# 3v_i2c_Bean_OLED_Rev1_1.net
KiCad netlist of a schematic drawn in Altium Designer
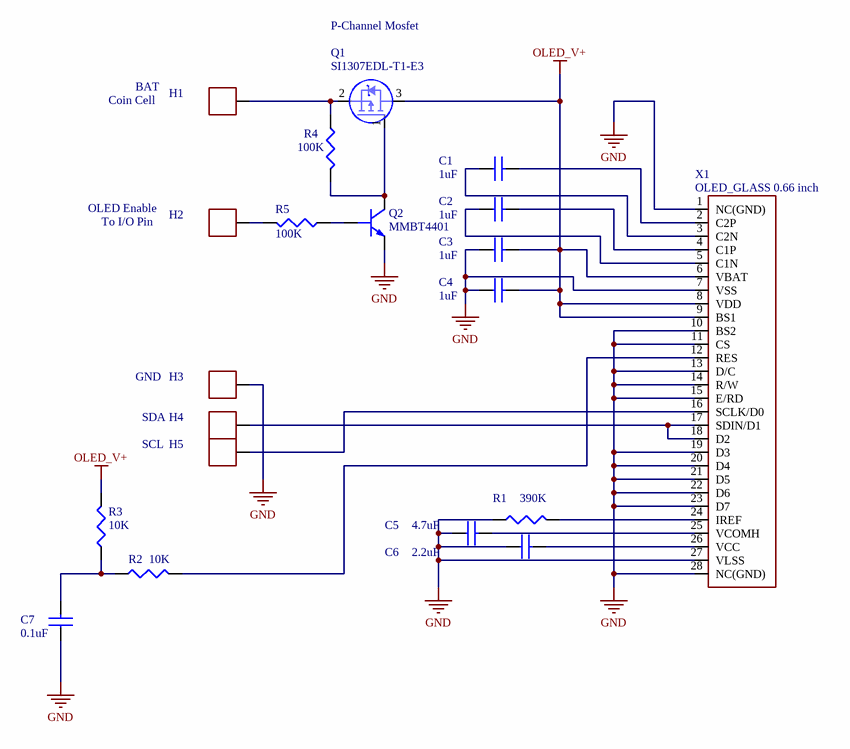
[diagram p0: 3v_i2c_Bean_OLED_Rev1.1.SchDoc]

(export (version "E")
  (design (tool "Eeschema 10.0.6"))
  (components
    (comp (ref "C1")
      (value "1uF")
      (footprint "CAPC1608X09L")
      (description "CAP 0603")
      (libsource (lib "Parts_Library") (part "CAP_0603"))
    )
    (comp (ref "C2")
      (value "1uF")
      (footprint "CAPC1608X09L")
      (description "CAP 0603")
      (libsource (lib "Parts_Library") (part "CAP_0603"))
    )
    (comp (ref "C3")
      (value "1uF")
      (footprint "CAPC1608X09L")
      (description "CAP 0603")
      (libsource (lib "Parts_Library") (part "CAP_0603"))
    )
    (comp (ref "C4")
      (value "1uF")
      (footprint "CAPC1608X09L")
      (description "CAP 0603")
      (libsource (lib "Parts_Library") (part "CAP_0603"))
    )
    (comp (ref "C5")
      (value "4.7uF")
      (footprint "CAPC1608X09L")
      (description "CAP 0603")
      (libsource (lib "Parts_Library") (part "CAP_0603"))
    )
    (comp (ref "C6")
      (value "2.2uF")
      (footprint "CAPC1608X09L")
      (description "CAP 0603")
      (libsource (lib "Parts_Library") (part "CAP_0603"))
    )
    (comp (ref "C7")
      (value "0.1uF")
      (footprint "CAPC1608X09L")
      (description "CAP 0603")
      (libsource (lib "Parts_Library") (part "CAP_0603"))
    )
    (comp (ref "H1")
      (value "CON1")
      (footprint "HDR1X1")
      (description "CONN HEADER 1POS .100\" PADS")
      (fields (field (name "PARTNUMBER") "PADS"))
      (libsource (lib "MAR") (part "CON1"))
    )
    (comp (ref "H2")
      (value "CON1")
      (footprint "HDR1X1")
      (description "CONN HEADER 1POS .100\" PADS")
      (fields (field (name "PARTNUMBER") "PADS"))
      (libsource (lib "MAR") (part "CON1"))
    )
    (comp (ref "H3")
      (value "CON1")
      (footprint "HDR1X1")
      (description "CONN HEADER 1POS .100\" PADS")
      (fields (field (name "PARTNUMBER") "PADS"))
      (libsource (lib "MAR") (part "CON1"))
    )
    (comp (ref "H4")
      (value "CON1")
      (footprint "HDR1X1")
      (description "CONN HEADER 1POS .100\" PADS")
      (fields (field (name "PARTNUMBER") "PADS"))
      (libsource (lib "MAR") (part "CON1"))
    )
    (comp (ref "H5")
      (value "CON1")
      (footprint "HDR1X1")
      (description "CONN HEADER 1POS .100\" PADS")
      (fields (field (name "PARTNUMBER") "PADS"))
      (libsource (lib "MAR") (part "CON1"))
    )
    (comp (ref "Q1")
      (value "~")
      (footprint "SC70-LB3_N")
      (description "MOSFET P-CH 12V 850MA SOT323-3")
      (fields (field (name "MANUFACTURER") "Vishay") (field (name "PARTNUMBER") "SI1307EDL-T1-E3"))
      (libsource (lib "MAR") (part "SI1307EDL-T1-E3"))
    )
    (comp (ref "Q2")
      (value "MMBT4401")
      (footprint "SOT95P240X110-3N")
      (description "TRANSISTOR GP NPN AMP SOT-23")
      (fields (field (name "MANUFACTURER") "Fairchild Semi") (field (name "PARTNUMBER") "MMBT4401"))
      (libsource (lib "MAR") (part "MMBT4401"))
    )
    (comp (ref "R1")
      (value "390K")
      (footprint "RESC1608X06L")
      (description "RES 0603")
      (libsource (lib "Parts_Library") (part "RES_0603"))
    )
    (comp (ref "R2")
      (value "10K")
      (footprint "RESC1608X06L")
      (description "RES 0603")
      (libsource (lib "Parts_Library") (part "RES_0603"))
    )
    (comp (ref "R3")
      (value "10K")
      (footprint "RESC1608X06L")
      (description "RES 0603")
      (libsource (lib "Parts_Library") (part "RES_0603"))
    )
    (comp (ref "R4")
      (value "100K")
      (footprint "RESC1608X06L")
      (description "RES 100K OHM 1/10W 1% 0603 SMD")
      (libsource (lib "Parts_Library") (part "RES_0603"))
    )
    (comp (ref "R5")
      (value "100K")
      (footprint "RESC1608X06L")
      (description "RES 100K OHM 1/10W 1% 0603 SMD")
      (libsource (lib "Parts_Library") (part "RES_0603"))
    )
    (comp (ref "X1")
      (value "OLED_GLASS 0.66 inch")
      (footprint "OLED_GLASS 0.66 INCH")
      (description "0.66 inch OLED_GLASS")
      (libsource (lib "MAR") (part "OLED_GLASS 0.66 inch"))
    )
  )
  (nets
    (net (code "1") (name "GND") (class "Default")
      (node (ref "C3") (pin "1") (pinfunction "1_1") (pintype "passive"))
      (node (ref "C4") (pin "1") (pinfunction "1_1") (pintype "passive"))
      (node (ref "C5") (pin "1") (pinfunction "1_1") (pintype "passive"))
      (node (ref "C6") (pin "1") (pinfunction "1_1") (pintype "passive"))
      (node (ref "C7") (pin "1") (pinfunction "1_1") (pintype "passive"))
      (node (ref "H3") (pin "1") (pintype "passive"))
      (node (ref "Q2") (pin "2") (pinfunction "E_2") (pintype "passive"))
      (node (ref "R1") (pin "1") (pinfunction "1_1") (pintype "passive"))
      (node (ref "X1") (pin "1") (pinfunction "NC(GND)_1") (pintype "passive"))
      (node (ref "X1") (pin "10") (pinfunction "BS2_10") (pintype "passive"))
      (node (ref "X1") (pin "11") (pinfunction "CS_11") (pintype "passive"))
      (node (ref "X1") (pin "13") (pinfunction "D/C_13") (pintype "passive"))
      (node (ref "X1") (pin "14") (pinfunction "R/W_14") (pintype "passive"))
      (node (ref "X1") (pin "15") (pinfunction "E/RD_15") (pintype "passive"))
      (node (ref "X1") (pin "19") (pinfunction "D3_19") (pintype "passive"))
      (node (ref "X1") (pin "20") (pinfunction "D4_20") (pintype "passive"))
      (node (ref "X1") (pin "21") (pinfunction "D5_21") (pintype "passive"))
      (node (ref "X1") (pin "22") (pinfunction "D6_22") (pintype "passive"))
      (node (ref "X1") (pin "23") (pinfunction "D7_23") (pintype "passive"))
      (node (ref "X1") (pin "27") (pinfunction "VLSS_27") (pintype "passive"))
      (node (ref "X1") (pin "28") (pinfunction "NC(GND)_28") (pintype "passive"))
      (node (ref "X1") (pin "7") (pinfunction "VSS_7") (pintype "passive"))
    )
    (net (code "2") (name "Net-(C7-Pad2)") (class "Default")
      (node (ref "C7") (pin "2") (pinfunction "2_2") (pintype "passive"))
      (node (ref "R2") (pin "1") (pinfunction "1_1") (pintype "passive"))
      (node (ref "R3") (pin "1") (pinfunction "1_1") (pintype "passive"))
    )
    (net (code "3") (name "Net-(H2-Pad1)") (class "Default")
      (node (ref "H2") (pin "1") (pintype "passive"))
      (node (ref "R5") (pin "2") (pinfunction "2_2") (pintype "passive"))
    )
    (net (code "4") (name "Net-(Q1-G)") (class "Default")
      (node (ref "Q1") (pin "1") (pinfunction "G_1") (pintype "passive"))
      (node (ref "Q2") (pin "3") (pinfunction "C_3") (pintype "passive"))
      (node (ref "R4") (pin "2") (pinfunction "2_2") (pintype "passive"))
    )
    (net (code "5") (name "Net-(Q1-S)") (class "Default")
      (node (ref "H1") (pin "1") (pintype "passive"))
      (node (ref "Q1") (pin "2") (pinfunction "S_2") (pintype "passive"))
      (node (ref "R4") (pin "1") (pinfunction "1_1") (pintype "passive"))
    )
    (net (code "6") (name "Net-(Q2-B)") (class "Default")
      (node (ref "Q2") (pin "1") (pinfunction "B_1") (pintype "passive"))
      (node (ref "R5") (pin "1") (pinfunction "1_1") (pintype "passive"))
    )
    (net (code "7") (name "Net-(X1-C1N)") (class "Default")
      (node (ref "C2") (pin "1") (pinfunction "1_1") (pintype "passive"))
      (node (ref "X1") (pin "5") (pinfunction "C1N_5") (pintype "passive"))
    )
    (net (code "8") (name "Net-(X1-C1P)") (class "Default")
      (node (ref "C2") (pin "2") (pinfunction "2_2") (pintype "passive"))
      (node (ref "X1") (pin "4") (pinfunction "C1P_4") (pintype "passive"))
    )
    (net (code "9") (name "Net-(X1-C2N)") (class "Default")
      (node (ref "C1") (pin "1") (pinfunction "1_1") (pintype "passive"))
      (node (ref "X1") (pin "3") (pinfunction "C2N_3") (pintype "passive"))
    )
    (net (code "10") (name "Net-(X1-C2P)") (class "Default")
      (node (ref "C1") (pin "2") (pinfunction "2_2") (pintype "passive"))
      (node (ref "X1") (pin "2") (pinfunction "C2P_2") (pintype "passive"))
    )
    (net (code "11") (name "Net-(X1-D2)") (class "Default")
      (node (ref "H4") (pin "1") (pintype "passive"))
      (node (ref "X1") (pin "17") (pinfunction "SDIN/D1_17") (pintype "passive"))
      (node (ref "X1") (pin "18") (pinfunction "D2_18") (pintype "passive"))
    )
    (net (code "12") (name "Net-(X1-IREF)") (class "Default")
      (node (ref "R1") (pin "2") (pinfunction "2_2") (pintype "passive"))
      (node (ref "X1") (pin "24") (pinfunction "IREF_24") (pintype "passive"))
    )
    (net (code "13") (name "Net-(X1-RES)") (class "Default")
      (node (ref "R2") (pin "2") (pinfunction "2_2") (pintype "passive"))
      (node (ref "X1") (pin "12") (pinfunction "RES_12") (pintype "passive"))
    )
    (net (code "14") (name "Net-(X1-SCLK{slash}D0)") (class "Default")
      (node (ref "H5") (pin "1") (pintype "passive"))
      (node (ref "X1") (pin "16") (pinfunction "SCLK/D0_16") (pintype "passive"))
    )
    (net (code "15") (name "Net-(X1-VCC)") (class "Default")
      (node (ref "C6") (pin "2") (pinfunction "2_2") (pintype "passive"))
      (node (ref "X1") (pin "26") (pinfunction "VCC_26") (pintype "passive"))
    )
    (net (code "16") (name "Net-(X1-VCOMH)") (class "Default")
      (node (ref "C5") (pin "2") (pinfunction "2_2") (pintype "passive"))
      (node (ref "X1") (pin "25") (pinfunction "VCOMH_25") (pintype "passive"))
    )
    (net (code "17") (name "OLED_V+") (class "Default")
      (node (ref "C3") (pin "2") (pinfunction "2_2") (pintype "passive"))
      (node (ref "C4") (pin "2") (pinfunction "2_2") (pintype "passive"))
      (node (ref "Q1") (pin "3") (pinfunction "D_3") (pintype "passive"))
      (node (ref "R3") (pin "2") (pinfunction "2_2") (pintype "passive"))
      (node (ref "X1") (pin "6") (pinfunction "VBAT_6") (pintype "passive"))
      (node (ref "X1") (pin "8") (pinfunction "VDD_8") (pintype "passive"))
      (node (ref "X1") (pin "9") (pinfunction "BS1_9") (pintype "passive"))
    )
  )
)
